# Plipbox.net
KiCad netlist of a schematic drawn in EAGLE
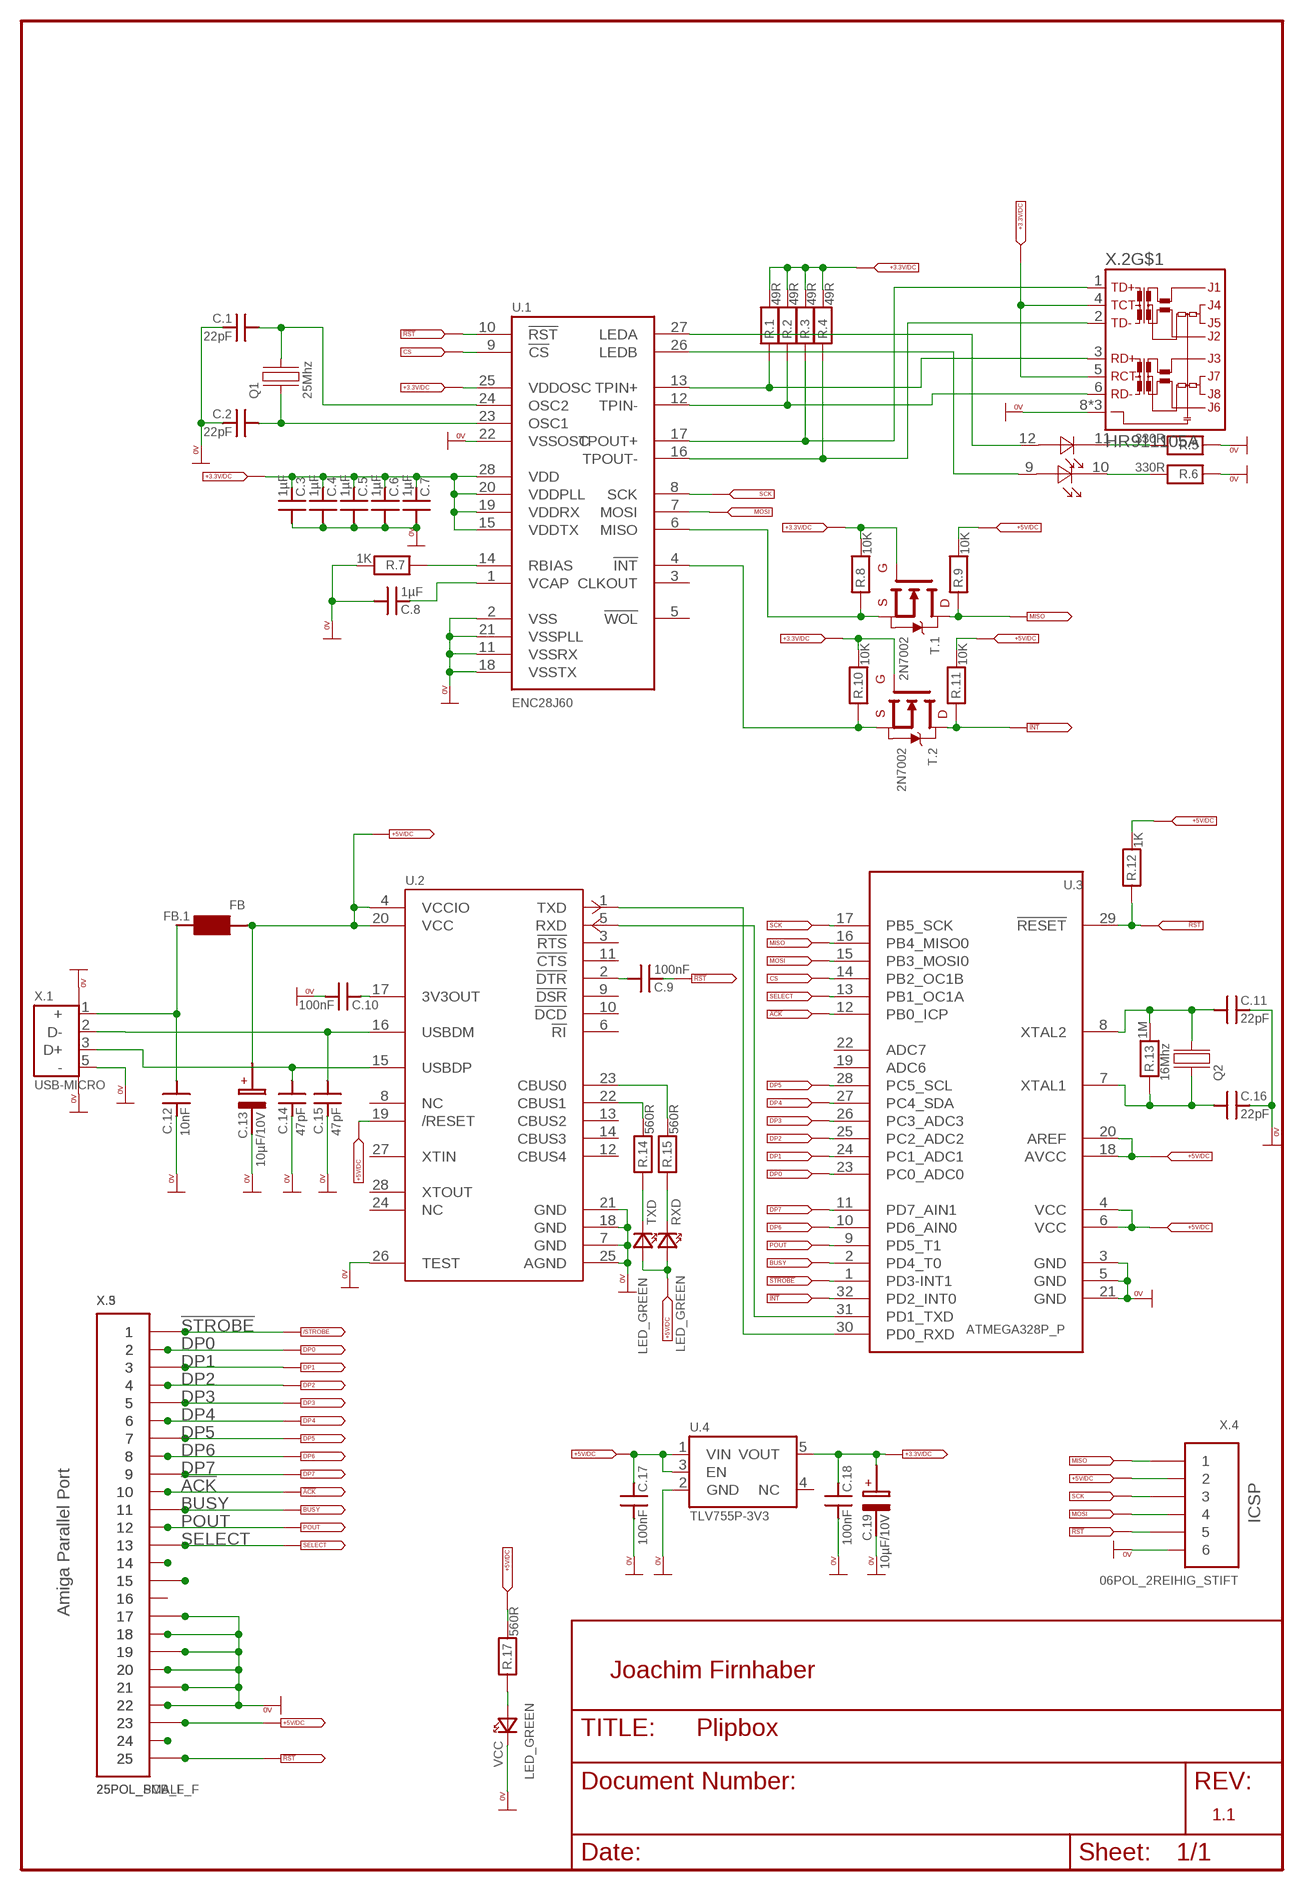
[diagram p0: schematic, sheet 1]

(export (version "E")
  (design (tool "Eeschema 10.0.6"))
  (components
    (comp (ref "C.1")
      (value "22pF")
      (footprint "eagle-import:0805")
      (libsource (lib "eagle-import") (part "CAPACITOR_SMD_0805"))
    )
    (comp (ref "C.2")
      (value "22pF")
      (footprint "eagle-import:0805")
      (libsource (lib "eagle-import") (part "CAPACITOR_SMD_0805"))
    )
    (comp (ref "C.3")
      (value "1µF")
      (footprint "eagle-import:0805")
      (libsource (lib "eagle-import") (part "CAPACITOR_SMD_0805"))
    )
    (comp (ref "C.4")
      (value "1µF")
      (footprint "eagle-import:0805")
      (libsource (lib "eagle-import") (part "CAPACITOR_SMD_0805"))
    )
    (comp (ref "C.5")
      (value "1µF")
      (footprint "eagle-import:0805")
      (libsource (lib "eagle-import") (part "CAPACITOR_SMD_0805"))
    )
    (comp (ref "C.6")
      (value "1µF")
      (footprint "eagle-import:0805")
      (libsource (lib "eagle-import") (part "CAPACITOR_SMD_0805"))
    )
    (comp (ref "C.7")
      (value "1µF")
      (footprint "eagle-import:0805")
      (libsource (lib "eagle-import") (part "CAPACITOR_SMD_0805"))
    )
    (comp (ref "C.8")
      (value "1µF")
      (footprint "eagle-import:0805")
      (libsource (lib "eagle-import") (part "CAPACITOR_SMD_0805"))
    )
    (comp (ref "C.9")
      (value "100nF")
      (footprint "eagle-import:0805")
      (libsource (lib "eagle-import") (part "CAPACITOR_SMD_0805"))
    )
    (comp (ref "C.10")
      (value "100nF")
      (footprint "eagle-import:0805")
      (libsource (lib "eagle-import") (part "CAPACITOR_SMD_0805"))
    )
    (comp (ref "C.11")
      (value "22pF")
      (footprint "eagle-import:0805")
      (libsource (lib "eagle-import") (part "CAPACITOR_SMD_0805"))
    )
    (comp (ref "C.12")
      (value "10nF")
      (footprint "eagle-import:0805")
      (libsource (lib "eagle-import") (part "CAPACITOR_SMD_0805"))
    )
    (comp (ref "C.13")
      (value "10µF/10V")
      (footprint "eagle-import:3216")
      (libsource (lib "eagle-import") (part "TANTAL_SMD_A(3216)"))
    )
    (comp (ref "C.14")
      (value "47pF")
      (footprint "eagle-import:0805")
      (libsource (lib "eagle-import") (part "CAPACITOR_SMD_0805"))
    )
    (comp (ref "C.15")
      (value "47pF")
      (footprint "eagle-import:0805")
      (libsource (lib "eagle-import") (part "CAPACITOR_SMD_0805"))
    )
    (comp (ref "C.16")
      (value "22pF")
      (footprint "eagle-import:0805")
      (libsource (lib "eagle-import") (part "CAPACITOR_SMD_0805"))
    )
    (comp (ref "C.17")
      (value "100nF")
      (footprint "eagle-import:0805")
      (libsource (lib "eagle-import") (part "CAPACITOR_SMD_0805"))
    )
    (comp (ref "C.18")
      (value "100nF")
      (footprint "eagle-import:0805")
      (libsource (lib "eagle-import") (part "CAPACITOR_SMD_0805"))
    )
    (comp (ref "C.19")
      (value "10µF/10V")
      (footprint "eagle-import:3216")
      (libsource (lib "eagle-import") (part "TANTAL_SMD_A(3216)"))
    )
    (comp (ref "FB.1")
      (value "FB")
      (footprint "eagle-import:0805")
      (libsource (lib "eagle-import") (part "FERRIT-BEAD"))
    )
    (comp (ref "Q1")
      (value "25Mhz")
      (footprint "eagle-import:3,4X2,7X0,75")
      (libsource (lib "eagle-import") (part "QUARZ_3,4X2,7"))
    )
    (comp (ref "Q2")
      (value "16Mhz")
      (footprint "eagle-import:3,4X2,7X0,75")
      (libsource (lib "eagle-import") (part "QUARZ_3,4X2,7"))
    )
    (comp (ref "R.1")
      (value "49R")
      (footprint "eagle-import:0805")
      (libsource (lib "eagle-import") (part "RESISTOR_SMD_0805"))
    )
    (comp (ref "R.2")
      (value "49R")
      (footprint "eagle-import:0805")
      (libsource (lib "eagle-import") (part "RESISTOR_SMD_0805"))
    )
    (comp (ref "R.3")
      (value "49R")
      (footprint "eagle-import:0805")
      (libsource (lib "eagle-import") (part "RESISTOR_SMD_0805"))
    )
    (comp (ref "R.4")
      (value "49R")
      (footprint "eagle-import:0805")
      (libsource (lib "eagle-import") (part "RESISTOR_SMD_0805"))
    )
    (comp (ref "R.5")
      (value "330R")
      (footprint "eagle-import:0805")
      (libsource (lib "eagle-import") (part "RESISTOR_SMD_0805"))
    )
    (comp (ref "R.6")
      (value "330R")
      (footprint "eagle-import:0805")
      (libsource (lib "eagle-import") (part "RESISTOR_SMD_0805"))
    )
    (comp (ref "R.7")
      (value "1K")
      (footprint "eagle-import:0805")
      (libsource (lib "eagle-import") (part "RESISTOR_SMD_0805"))
    )
    (comp (ref "R.8")
      (value "10K")
      (footprint "eagle-import:0805")
      (libsource (lib "eagle-import") (part "RESISTOR_SMD_0805"))
    )
    (comp (ref "R.9")
      (value "10K")
      (footprint "eagle-import:0805")
      (libsource (lib "eagle-import") (part "RESISTOR_SMD_0805"))
    )
    (comp (ref "R.10")
      (value "10K")
      (footprint "eagle-import:0805")
      (libsource (lib "eagle-import") (part "RESISTOR_SMD_0805"))
    )
    (comp (ref "R.11")
      (value "10K")
      (footprint "eagle-import:0805")
      (libsource (lib "eagle-import") (part "RESISTOR_SMD_0805"))
    )
    (comp (ref "R.12")
      (value "1K")
      (footprint "eagle-import:0805")
      (libsource (lib "eagle-import") (part "RESISTOR_SMD_0805"))
    )
    (comp (ref "R.13")
      (value "1M")
      (footprint "eagle-import:0805")
      (libsource (lib "eagle-import") (part "RESISTOR_SMD_0805"))
    )
    (comp (ref "R.14")
      (value "560R")
      (footprint "eagle-import:0805")
      (libsource (lib "eagle-import") (part "RESISTOR_SMD_0805"))
    )
    (comp (ref "R.15")
      (value "560R")
      (footprint "eagle-import:0805")
      (libsource (lib "eagle-import") (part "RESISTOR_SMD_0805"))
    )
    (comp (ref "R.17")
      (value "560R")
      (footprint "eagle-import:0805")
      (libsource (lib "eagle-import") (part "RESISTOR_SMD_0805"))
    )
    (comp (ref "RXD")
      (value "LED_GREEN")
      (footprint "eagle-import:0805")
      (libsource (lib "eagle-import") (part "LED_0805"))
    )
    (comp (ref "T.1")
      (value "2N7002")
      (footprint "eagle-import:SOT23")
      (libsource (lib "eagle-import") (part "2N7002_N"))
    )
    (comp (ref "T.2")
      (value "2N7002")
      (footprint "eagle-import:SOT23")
      (libsource (lib "eagle-import") (part "2N7002_N"))
    )
    (comp (ref "TXD")
      (value "LED_GREEN")
      (footprint "eagle-import:0805")
      (libsource (lib "eagle-import") (part "LED_0805"))
    )
    (comp (ref "U.1")
      (value "ENC28J60")
      (footprint "eagle-import:SSOP28")
      (libsource (lib "eagle-import") (part "EN28J60"))
    )
    (comp (ref "U.2")
      (value "FT232R_FT232RL")
      (footprint "eagle-import:SSOP28")
      (libsource (lib "eagle-import") (part "FT232R_FT232RL"))
    )
    (comp (ref "U.3")
      (value "ATMEGA328P_P")
      (footprint "eagle-import:LQFP32")
      (libsource (lib "eagle-import") (part "ATMEGA328P_P"))
    )
    (comp (ref "U.4")
      (value "TLV755P-3V3")
      (footprint "eagle-import:SOT23-5")
      (libsource (lib "eagle-import") (part "TLV755P"))
    )
    (comp (ref "VCC")
      (value "LED_GREEN")
      (footprint "eagle-import:0805")
      (libsource (lib "eagle-import") (part "LED_0805"))
    )
    (comp (ref "X.1")
      (value "USB-MICRO")
      (footprint "eagle-import:USB_MICRO")
      (libsource (lib "eagle-import") (part "USB-MICRO"))
    )
    (comp (ref "X.2")
      (value "HR911105A")
      (footprint "eagle-import:HR911105A")
      (libsource (lib "eagle-import") (part "HR911105A"))
    )
    (comp (ref "X.3")
      (value "25POL_PCB_F")
      (footprint "eagle-import:SUB-D_25F_L")
      (libsource (lib "eagle-import") (part "25POL_PCB_F"))
    )
    (comp (ref "X.4")
      (value "06POL_2REIHIG_STIFT")
      (footprint "eagle-import:STIFT_2_03")
      (libsource (lib "eagle-import") (part "06POL_2REIHIG_STIFT"))
    )
    (comp (ref "X.5")
      (value "25POL_SMALL_F")
      (footprint "eagle-import:SUB-D_25F_ONLY")
      (libsource (lib "eagle-import") (part "25POL_SMALL_F"))
    )
  )
  (nets
    (net (code "1") (name "!ACK") (class "Default")
      (node (ref "U.3") (pin "12") (pinfunction "PB0_ICP_12") (pintype "bidirectional"))
      (node (ref "X.3") (pin "10") (pinfunction "10_10") (pintype "passive"))
      (node (ref "X.5") (pin "10") (pinfunction "10_10") (pintype "passive"))
    )
    (net (code "2") (name "!INT") (class "Default")
      (node (ref "R.11") (pin "1") (pinfunction "1_1") (pintype "passive"))
      (node (ref "T.2") (pin "3") (pinfunction "DRAIN_3") (pintype "passive"))
      (node (ref "U.3") (pin "32") (pinfunction "PD2_INT0_32") (pintype "bidirectional"))
    )
    (net (code "3") (name "!RST") (class "Default")
      (node (ref "C.9") (pin "2") (pinfunction "2_2") (pintype "passive"))
      (node (ref "R.12") (pin "1") (pinfunction "1_1") (pintype "passive"))
      (node (ref "U.1") (pin "10") (pinfunction "~{RST}_10") (pintype "bidirectional"))
      (node (ref "U.3") (pin "29") (pinfunction "~{RESET}_29") (pintype "bidirectional"))
      (node (ref "X.3") (pin "25") (pinfunction "25_25") (pintype "passive"))
      (node (ref "X.4") (pin "5") (pinfunction "5_5") (pintype "passive"))
      (node (ref "X.5") (pin "25") (pinfunction "25_25") (pintype "passive"))
    )
    (net (code "4") (name "!STROBE") (class "Default")
      (node (ref "U.3") (pin "1") (pinfunction "PD3-INT1_1") (pintype "bidirectional"))
      (node (ref "X.3") (pin "1") (pinfunction "1_1") (pintype "passive"))
      (node (ref "X.5") (pin "1") (pinfunction "1_1") (pintype "passive"))
    )
    (net (code "5") (name "+3.3V-IN") (class "Default")
      (node (ref "C.18") (pin "2") (pinfunction "2_2") (pintype "passive"))
      (node (ref "C.19") (pin "+") (pinfunction "+_+") (pintype "passive"))
      (node (ref "C.3") (pin "2") (pinfunction "2_2") (pintype "passive"))
      (node (ref "C.4") (pin "2") (pinfunction "2_2") (pintype "passive"))
      (node (ref "C.5") (pin "2") (pinfunction "2_2") (pintype "passive"))
      (node (ref "C.6") (pin "2") (pinfunction "2_2") (pintype "passive"))
      (node (ref "C.7") (pin "2") (pinfunction "2_2") (pintype "passive"))
      (node (ref "R.1") (pin "2") (pinfunction "2_2") (pintype "passive"))
      (node (ref "R.10") (pin "2") (pinfunction "2_2") (pintype "passive"))
      (node (ref "R.2") (pin "2") (pinfunction "2_2") (pintype "passive"))
      (node (ref "R.3") (pin "2") (pinfunction "2_2") (pintype "passive"))
      (node (ref "R.4") (pin "2") (pinfunction "2_2") (pintype "passive"))
      (node (ref "R.8") (pin "2") (pinfunction "2_2") (pintype "passive"))
      (node (ref "T.1") (pin "1") (pinfunction "GATE_1") (pintype "passive"))
      (node (ref "T.2") (pin "1") (pinfunction "GATE_1") (pintype "passive"))
      (node (ref "U.1") (pin "15") (pinfunction "VDDTX_15") (pintype "bidirectional"))
      (node (ref "U.1") (pin "19") (pinfunction "VDDRX_19") (pintype "bidirectional"))
      (node (ref "U.1") (pin "20") (pinfunction "VDDPLL_20") (pintype "bidirectional"))
      (node (ref "U.1") (pin "25") (pinfunction "VDDOSC_25") (pintype "bidirectional"))
      (node (ref "U.1") (pin "28") (pinfunction "VDD_28") (pintype "bidirectional"))
      (node (ref "U.4") (pin "5") (pinfunction "VOUT_5") (pintype "bidirectional"))
      (node (ref "X.2") (pin "4") (pinfunction "TCT-_4") (pintype "passive"))
      (node (ref "X.2") (pin "5") (pinfunction "RCT-_5") (pintype "passive"))
    )
    (net (code "6") (name "+5V-IN") (class "Default")
      (node (ref "C.13") (pin "+") (pinfunction "+_+") (pintype "passive"))
      (node (ref "C.17") (pin "2") (pinfunction "2_2") (pintype "passive"))
      (node (ref "FB.1") (pin "1") (pinfunction "1_1") (pintype "passive"))
      (node (ref "R.11") (pin "2") (pinfunction "2_2") (pintype "passive"))
      (node (ref "R.12") (pin "2") (pinfunction "2_2") (pintype "passive"))
      (node (ref "R.17") (pin "2") (pinfunction "2_2") (pintype "passive"))
      (node (ref "R.9") (pin "2") (pinfunction "2_2") (pintype "passive"))
      (node (ref "RXD") (pin "A") (pinfunction "ANODE_A") (pintype "passive"))
      (node (ref "TXD") (pin "A") (pinfunction "ANODE_A") (pintype "passive"))
      (node (ref "U.2") (pin "19") (pinfunction "/RESET_19") (pintype "bidirectional"))
      (node (ref "U.2") (pin "20") (pinfunction "VCC_20") (pintype "bidirectional"))
      (node (ref "U.2") (pin "4") (pinfunction "VCCIO_4") (pintype "bidirectional"))
      (node (ref "U.3") (pin "18") (pinfunction "AVCC_18") (pintype "bidirectional"))
      (node (ref "U.3") (pin "20") (pinfunction "AREF_20") (pintype "bidirectional"))
      (node (ref "U.3") (pin "4") (pinfunction "VCC_4") (pintype "bidirectional"))
      (node (ref "U.3") (pin "6") (pinfunction "VCC_6") (pintype "bidirectional"))
      (node (ref "U.4") (pin "1") (pinfunction "VIN_1") (pintype "bidirectional"))
      (node (ref "U.4") (pin "3") (pinfunction "EN_3") (pintype "bidirectional"))
      (node (ref "X.3") (pin "23") (pinfunction "23_23") (pintype "passive"))
      (node (ref "X.4") (pin "2") (pinfunction "2_2") (pintype "passive"))
      (node (ref "X.5") (pin "23") (pinfunction "23_23") (pintype "passive"))
    )
    (net (code "7") (name "0V") (class "Default")
      (node (ref "C.1") (pin "2") (pinfunction "2_2") (pintype "passive"))
      (node (ref "C.10") (pin "1") (pinfunction "1_1") (pintype "passive"))
      (node (ref "C.11") (pin "2") (pinfunction "2_2") (pintype "passive"))
      (node (ref "C.12") (pin "2") (pinfunction "2_2") (pintype "passive"))
      (node (ref "C.13") (pin "-") (pinfunction "-_-") (pintype "passive"))
      (node (ref "C.14") (pin "2") (pinfunction "2_2") (pintype "passive"))
      (node (ref "C.15") (pin "2") (pinfunction "2_2") (pintype "passive"))
      (node (ref "C.16") (pin "2") (pinfunction "2_2") (pintype "passive"))
      (node (ref "C.17") (pin "1") (pinfunction "1_1") (pintype "passive"))
      (node (ref "C.18") (pin "1") (pinfunction "1_1") (pintype "passive"))
      (node (ref "C.19") (pin "-") (pinfunction "-_-") (pintype "passive"))
      (node (ref "C.2") (pin "2") (pinfunction "2_2") (pintype "passive"))
      (node (ref "C.3") (pin "1") (pinfunction "1_1") (pintype "passive"))
      (node (ref "C.4") (pin "1") (pinfunction "1_1") (pintype "passive"))
      (node (ref "C.5") (pin "1") (pinfunction "1_1") (pintype "passive"))
      (node (ref "C.6") (pin "1") (pinfunction "1_1") (pintype "passive"))
      (node (ref "C.7") (pin "1") (pinfunction "1_1") (pintype "passive"))
      (node (ref "C.8") (pin "1") (pinfunction "1_1") (pintype "passive"))
      (node (ref "R.5") (pin "1") (pinfunction "1_1") (pintype "passive"))
      (node (ref "R.6") (pin "1") (pinfunction "1_1") (pintype "passive"))
      (node (ref "R.7") (pin "2") (pinfunction "2_2") (pintype "passive"))
      (node (ref "U.1") (pin "11") (pinfunction "VSSRX_11") (pintype "bidirectional"))
      (node (ref "U.1") (pin "18") (pinfunction "VSSTX_18") (pintype "bidirectional"))
      (node (ref "U.1") (pin "2") (pinfunction "VSS_2") (pintype "bidirectional"))
      (node (ref "U.1") (pin "21") (pinfunction "VSSPLL_21") (pintype "bidirectional"))
      (node (ref "U.1") (pin "22") (pinfunction "VSSOSC_22") (pintype "bidirectional"))
      (node (ref "U.2") (pin "18") (pinfunction "GND_18") (pintype "bidirectional"))
      (node (ref "U.2") (pin "21") (pinfunction "GND_21") (pintype "bidirectional"))
      (node (ref "U.2") (pin "25") (pinfunction "AGND_25") (pintype "bidirectional"))
      (node (ref "U.2") (pin "26") (pinfunction "TEST_26") (pintype "bidirectional"))
      (node (ref "U.2") (pin "7") (pinfunction "GND_7") (pintype "bidirectional"))
      (node (ref "U.3") (pin "21") (pinfunction "GND_21") (pintype "bidirectional"))
      (node (ref "U.3") (pin "3") (pinfunction "GND_3") (pintype "bidirectional"))
      (node (ref "U.3") (pin "5") (pinfunction "GND_5") (pintype "bidirectional"))
      (node (ref "U.4") (pin "2") (pinfunction "GND_2") (pintype "bidirectional"))
      (node (ref "VCC") (pin "K") (pinfunction "KATHODE_K") (pintype "passive"))
      (node (ref "X.1") (pin "5") (pinfunction "-_5") (pintype "bidirectional"))
      (node (ref "X.1") (pin "6") (pinfunction "GND_6") (pintype "bidirectional"))
      (node (ref "X.1") (pin "7") (pinfunction "GND_7") (pintype "bidirectional"))
      (node (ref "X.2") (pin "8") (pinfunction "GND_8") (pintype "passive"))
      (node (ref "X.2") (pin "Z1") (pinfunction "GND_Z1") (pintype "passive"))
      (node (ref "X.2") (pin "Z2") (pinfunction "GND_Z2") (pintype "passive"))
      (node (ref "X.3") (pin "17") (pinfunction "17_17") (pintype "passive"))
      (node (ref "X.3") (pin "18") (pinfunction "18_18") (pintype "passive"))
      (node (ref "X.3") (pin "19") (pinfunction "19_19") (pintype "passive"))
      (node (ref "X.3") (pin "20") (pinfunction "20_20") (pintype "passive"))
      (node (ref "X.3") (pin "21") (pinfunction "21_21") (pintype "passive"))
      (node (ref "X.3") (pin "22") (pinfunction "22_22") (pintype "passive"))
      (node (ref "X.4") (pin "6") (pinfunction "6_6") (pintype "passive"))
      (node (ref "X.5") (pin "17") (pinfunction "17_17") (pintype "passive"))
      (node (ref "X.5") (pin "18") (pinfunction "18_18") (pintype "passive"))
      (node (ref "X.5") (pin "19") (pinfunction "19_19") (pintype "passive"))
      (node (ref "X.5") (pin "20") (pinfunction "20_20") (pintype "passive"))
      (node (ref "X.5") (pin "21") (pinfunction "21_21") (pintype "passive"))
      (node (ref "X.5") (pin "22") (pinfunction "22_22") (pintype "passive"))
    )
    (net (code "8") (name "BUSY") (class "Default")
      (node (ref "U.3") (pin "2") (pinfunction "PD4_T0_2") (pintype "bidirectional"))
      (node (ref "X.3") (pin "11") (pinfunction "11_11") (pintype "passive"))
      (node (ref "X.5") (pin "11") (pinfunction "11_11") (pintype "passive"))
    )
    (net (code "9") (name "CS") (class "Default")
      (node (ref "U.1") (pin "9") (pinfunction "~{CS}_9") (pintype "bidirectional"))
      (node (ref "U.3") (pin "14") (pinfunction "PB2_OC1B_14") (pintype "bidirectional"))
    )
    (net (code "10") (name "DP0") (class "Default")
      (node (ref "U.3") (pin "23") (pinfunction "PC0_ADC0_23") (pintype "bidirectional"))
      (node (ref "X.3") (pin "2") (pinfunction "2_2") (pintype "passive"))
      (node (ref "X.5") (pin "2") (pinfunction "2_2") (pintype "passive"))
    )
    (net (code "11") (name "DP1") (class "Default")
      (node (ref "U.3") (pin "24") (pinfunction "PC1_ADC1_24") (pintype "bidirectional"))
      (node (ref "X.3") (pin "3") (pinfunction "3_3") (pintype "passive"))
      (node (ref "X.5") (pin "3") (pinfunction "3_3") (pintype "passive"))
    )
    (net (code "12") (name "DP2") (class "Default")
      (node (ref "U.3") (pin "25") (pinfunction "PC2_ADC2_25") (pintype "bidirectional"))
      (node (ref "X.3") (pin "4") (pinfunction "4_4") (pintype "passive"))
      (node (ref "X.5") (pin "4") (pinfunction "4_4") (pintype "passive"))
    )
    (net (code "13") (name "DP3") (class "Default")
      (node (ref "U.3") (pin "26") (pinfunction "PC3_ADC3_26") (pintype "bidirectional"))
      (node (ref "X.3") (pin "5") (pinfunction "5_5") (pintype "passive"))
      (node (ref "X.5") (pin "5") (pinfunction "5_5") (pintype "passive"))
    )
    (net (code "14") (name "DP4") (class "Default")
      (node (ref "U.3") (pin "27") (pinfunction "PC4_SDA_27") (pintype "bidirectional"))
      (node (ref "X.3") (pin "6") (pinfunction "6_6") (pintype "passive"))
      (node (ref "X.5") (pin "6") (pinfunction "6_6") (pintype "passive"))
    )
    (net (code "15") (name "DP5") (class "Default")
      (node (ref "U.3") (pin "28") (pinfunction "PC5_SCL_28") (pintype "bidirectional"))
      (node (ref "X.3") (pin "7") (pinfunction "7_7") (pintype "passive"))
      (node (ref "X.5") (pin "7") (pinfunction "7_7") (pintype "passive"))
    )
    (net (code "16") (name "DP6") (class "Default")
      (node (ref "U.3") (pin "10") (pinfunction "PD6_AIN0_10") (pintype "bidirectional"))
      (node (ref "X.3") (pin "8") (pinfunction "8_8") (pintype "passive"))
      (node (ref "X.5") (pin "8") (pinfunction "8_8") (pintype "passive"))
    )
    (net (code "17") (name "DP7") (class "Default")
      (node (ref "U.3") (pin "11") (pinfunction "PD7_AIN1_11") (pintype "bidirectional"))
      (node (ref "X.3") (pin "9") (pinfunction "9_9") (pintype "passive"))
      (node (ref "X.5") (pin "9") (pinfunction "9_9") (pintype "passive"))
    )
    (net (code "18") (name "MISO") (class "Default")
      (node (ref "R.9") (pin "1") (pinfunction "1_1") (pintype "passive"))
      (node (ref "T.1") (pin "3") (pinfunction "DRAIN_3") (pintype "passive"))
      (node (ref "U.3") (pin "16") (pinfunction "PB4_MISO0_16") (pintype "bidirectional"))
      (node (ref "X.4") (pin "1") (pinfunction "1_1") (pintype "passive"))
    )
    (net (code "19") (name "MOSI") (class "Default")
      (node (ref "U.1") (pin "7") (pinfunction "MOSI_7") (pintype "bidirectional"))
      (node (ref "U.3") (pin "15") (pinfunction "PB3_MOSI0_15") (pintype "bidirectional"))
      (node (ref "X.4") (pin "4") (pinfunction "4_4") (pintype "passive"))
    )
    (net (code "20") (name "Net-(Q1-XTAL1)") (class "Default")
      (node (ref "C.2") (pin "1") (pinfunction "1_1") (pintype "passive"))
      (node (ref "Q1") (pin "2") (pinfunction "XTAL1_2") (pintype "bidirectional"))
      (node (ref "U.1") (pin "23") (pinfunction "OSC1_23") (pintype "bidirectional"))
    )
    (net (code "21") (name "Net-(Q1-XTAL2)") (class "Default")
      (node (ref "C.1") (pin "1") (pinfunction "1_1") (pintype "passive"))
      (node (ref "Q1") (pin "4") (pinfunction "XTAL2_4") (pintype "bidirectional"))
      (node (ref "U.1") (pin "24") (pinfunction "OSC2_24") (pintype "bidirectional"))
    )
    (net (code "22") (name "Net-(Q2-XTAL1)") (class "Default")
      (node (ref "C.16") (pin "1") (pinfunction "1_1") (pintype "passive"))
      (node (ref "Q2") (pin "2") (pinfunction "XTAL1_2") (pintype "bidirectional"))
      (node (ref "R.13") (pin "1") (pinfunction "1_1") (pintype "passive"))
      (node (ref "U.3") (pin "7") (pinfunction "XTAL1_7") (pintype "bidirectional"))
    )
    (net (code "23") (name "Net-(Q2-XTAL2)") (class "Default")
      (node (ref "C.11") (pin "1") (pinfunction "1_1") (pintype "passive"))
      (node (ref "Q2") (pin "4") (pinfunction "XTAL2_4") (pintype "bidirectional"))
      (node (ref "R.13") (pin "2") (pinfunction "2_2") (pintype "passive"))
      (node (ref "U.3") (pin "8") (pinfunction "XTAL2_8") (pintype "bidirectional"))
    )
    (net (code "24") (name "Net-(RXD-KATHODE)") (class "Default")
      (node (ref "R.15") (pin "1") (pinfunction "1_1") (pintype "passive"))
      (node (ref "RXD") (pin "K") (pinfunction "KATHODE_K") (pintype "passive"))
    )
    (net (code "25") (name "Net-(T.1-SOURCE)") (class "Default")
      (node (ref "R.8") (pin "1") (pinfunction "1_1") (pintype "passive"))
      (node (ref "T.1") (pin "2") (pinfunction "SOURCE_2") (pintype "passive"))
      (node (ref "U.1") (pin "6") (pinfunction "MISO_6") (pintype "bidirectional"))
    )
    (net (code "26") (name "Net-(T.2-SOURCE)") (class "Default")
      (node (ref "R.10") (pin "1") (pinfunction "1_1") (pintype "passive"))
      (node (ref "T.2") (pin "2") (pinfunction "SOURCE_2") (pintype "passive"))
      (node (ref "U.1") (pin "4") (pinfunction "~{INT}_4") (pintype "bidirectional"))
    )
    (net (code "27") (name "Net-(TXD-KATHODE)") (class "Default")
      (node (ref "R.14") (pin "1") (pinfunction "1_1") (pintype "passive"))
      (node (ref "TXD") (pin "K") (pinfunction "KATHODE_K") (pintype "passive"))
    )
    (net (code "28") (name "Net-(U.1-LEDA)") (class "Default")
      (node (ref "U.1") (pin "27") (pinfunction "LEDA_27") (pintype "bidirectional"))
      (node (ref "X.2") (pin "12") (pinfunction "A_12") (pintype "bidirectional"))
    )
    (net (code "29") (name "Net-(U.1-LEDB)") (class "Default")
      (node (ref "U.1") (pin "26") (pinfunction "LEDB_26") (pintype "bidirectional"))
      (node (ref "X.2") (pin "9") (pinfunction "A_9") (pintype "bidirectional"))
    )
    (net (code "30") (name "Net-(U.1-RBIAS)") (class "Default")
      (node (ref "R.7") (pin "1") (pinfunction "1_1") (pintype "passive"))
      (node (ref "U.1") (pin "14") (pinfunction "RBIAS_14") (pintype "bidirectional"))
    )
    (net (code "31") (name "Net-(U.1-TPIN+)") (class "Default")
      (node (ref "R.1") (pin "1") (pinfunction "1_1") (pintype "passive"))
      (node (ref "U.1") (pin "13") (pinfunction "TPIN+_13") (pintype "bidirectional"))
      (node (ref "X.2") (pin "3") (pinfunction "RD+_3") (pintype "passive"))
    )
    (net (code "32") (name "Net-(U.1-TPIN-)") (class "Default")
      (node (ref "R.2") (pin "1") (pinfunction "1_1") (pintype "passive"))
      (node (ref "U.1") (pin "12") (pinfunction "TPIN-_12") (pintype "bidirectional"))
      (node (ref "X.2") (pin "6") (pinfunction "RD-_6") (pintype "passive"))
    )
    (net (code "33") (name "Net-(U.1-TPOUT+)") (class "Default")
      (node (ref "R.3") (pin "1") (pinfunction "1_1") (pintype "passive"))
      (node (ref "U.1") (pin "17") (pinfunction "TPOUT+_17") (pintype "bidirectional"))
      (node (ref "X.2") (pin "1") (pinfunction "TD+_1") (pintype "passive"))
    )
    (net (code "34") (name "Net-(U.1-TPOUT-)") (class "Default")
      (node (ref "R.4") (pin "1") (pinfunction "1_1") (pintype "passive"))
      (node (ref "U.1") (pin "16") (pinfunction "TPOUT-_16") (pintype "bidirectional"))
      (node (ref "X.2") (pin "2") (pinfunction "TD-_2") (pintype "passive"))
    )
    (net (code "35") (name "Net-(U.1-VCAP)") (class "Default")
      (node (ref "C.8") (pin "2") (pinfunction "2_2") (pintype "passive"))
      (node (ref "U.1") (pin "1") (pinfunction "VCAP_1") (pintype "bidirectional"))
    )
    (net (code "36") (name "Net-(U.2-3V3OUT)") (class "Default")
      (node (ref "C.10") (pin "2") (pinfunction "2_2") (pintype "passive"))
      (node (ref "U.2") (pin "17") (pinfunction "3V3OUT_17") (pintype "bidirectional"))
    )
    (net (code "37") (name "Net-(U.2-CBUS0)") (class "Default")
      (node (ref "R.15") (pin "2") (pinfunction "2_2") (pintype "passive"))
      (node (ref "U.2") (pin "23") (pinfunction "CBUS0_23") (pintype "bidirectional"))
    )
    (net (code "38") (name "Net-(U.2-CBUS1)") (class "Default")
      (node (ref "R.14") (pin "2") (pinfunction "2_2") (pintype "passive"))
      (node (ref "U.2") (pin "22") (pinfunction "CBUS1_22") (pintype "bidirectional"))
    )
    (net (code "39") (name "Net-(U.2-RXD)") (class "Default")
      (node (ref "U.2") (pin "5") (pinfunction "RXD_5") (pintype "bidirectional"))
      (node (ref "U.3") (pin "31") (pinfunction "PD1_TXD_31") (pintype "bidirectional"))
    )
    (net (code "40") (name "Net-(U.2-TXD)") (class "Default")
      (node (ref "U.2") (pin "1") (pinfunction "TXD_1") (pintype "bidirectional"))
      (node (ref "U.3") (pin "30") (pinfunction "PD0_RXD_30") (pintype "bidirectional"))
    )
    (net (code "41") (name "Net-(U.2-USBDM)") (class "Default")
      (node (ref "C.15") (pin "1") (pinfunction "1_1") (pintype "passive"))
      (node (ref "U.2") (pin "16") (pinfunction "USBDM_16") (pintype "bidirectional"))
      (node (ref "X.1") (pin "2") (pinfunction "D-_2") (pintype "bidirectional"))
    )
    (net (code "42") (name "Net-(U.2-USBDP)") (class "Default")
      (node (ref "C.14") (pin "1") (pinfunction "1_1") (pintype "passive"))
      (node (ref "U.2") (pin "15") (pinfunction "USBDP_15") (pintype "bidirectional"))
      (node (ref "X.1") (pin "3") (pinfunction "D+_3") (pintype "bidirectional"))
    )
    (net (code "43") (name "Net-(U.2-~{DTR})") (class "Default")
      (node (ref "C.9") (pin "1") (pinfunction "1_1") (pintype "passive"))
      (node (ref "U.2") (pin "2") (pinfunction "~{DTR}_2") (pintype "bidirectional"))
    )
    (net (code "44") (name "Net-(VCC-ANODE)") (class "Default")
      (node (ref "R.17") (pin "1") (pinfunction "1_1") (pintype "passive"))
      (node (ref "VCC") (pin "A") (pinfunction "ANODE_A") (pintype "passive"))
    )
    (net (code "45") (name "Net-(X.1-+)") (class "Default")
      (node (ref "C.12") (pin "1") (pinfunction "1_1") (pintype "passive"))
      (node (ref "FB.1") (pin "2") (pinfunction "2_2") (pintype "passive"))
      (node (ref "X.1") (pin "1") (pinfunction "+_1") (pintype "bidirectional"))
    )
    (net (code "46") (name "Net-(X.2B-K)") (class "Default")
      (node (ref "R.5") (pin "2") (pinfunction "2_2") (pintype "passive"))
      (node (ref "X.2") (pin "11") (pinfunction "K_11") (pintype "bidirectional"))
    )
    (net (code "47") (name "Net-(X.2C-K)") (class "Default")
      (node (ref "R.6") (pin "2") (pinfunction "2_2") (pintype "passive"))
      (node (ref "X.2") (pin "10") (pinfunction "K_10") (pintype "bidirectional"))
    )
    (net (code "48") (name "Net-(X.3-Pad14)") (class "Default")
      (node (ref "X.3") (pin "14") (pinfunction "14_14") (pintype "passive"))
      (node (ref "X.5") (pin "14") (pinfunction "14_14") (pintype "passive"))
    )
    (net (code "49") (name "Net-(X.3-Pad15)") (class "Default")
      (node (ref "X.3") (pin "15") (pinfunction "15_15") (pintype "passive"))
      (node (ref "X.5") (pin "15") (pinfunction "15_15") (pintype "passive"))
    )
    (net (code "50") (name "Net-(X.3-Pad16)") (class "Default")
      (node (ref "X.3") (pin "16") (pinfunction "16_16") (pintype "passive"))
      (node (ref "X.5") (pin "16") (pinfunction "16_16") (pintype "passive"))
    )
    (net (code "51") (name "Net-(X.3-Pad24)") (class "Default")
      (node (ref "X.3") (pin "24") (pinfunction "24_24") (pintype "passive"))
      (node (ref "X.5") (pin "24") (pinfunction "24_24") (pintype "passive"))
    )
    (net (code "52") (name "POUT") (class "Default")
      (node (ref "U.3") (pin "9") (pinfunction "PD5_T1_9") (pintype "bidirectional"))
      (node (ref "X.3") (pin "12") (pinfunction "12_12") (pintype "passive"))
      (node (ref "X.5") (pin "12") (pinfunction "12_12") (pintype "passive"))
    )
    (net (code "53") (name "SCK") (class "Default")
      (node (ref "U.1") (pin "8") (pinfunction "SCK_8") (pintype "bidirectional"))
      (node (ref "U.3") (pin "17") (pinfunction "PB5_SCK_17") (pintype "bidirectional"))
      (node (ref "X.4") (pin "3") (pinfunction "3_3") (pintype "passive"))
    )
    (net (code "54") (name "SELECT") (class "Default")
      (node (ref "U.3") (pin "13") (pinfunction "PB1_OC1A_13") (pintype "bidirectional"))
      (node (ref "X.3") (pin "13") (pinfunction "13_13") (pintype "passive"))
      (node (ref "X.5") (pin "13") (pinfunction "13_13") (pintype "passive"))
    )
    (net (code "55") (name "unconnected-(U.1-CLKOUT-Pad3)") (class "Default")
      (node (ref "U.1") (pin "3") (pinfunction "CLKOUT_3") (pintype "bidirectional"))
    )
    (net (code "56") (name "unconnected-(U.1-~{WOL}-Pad5)") (class "Default")
      (node (ref "U.1") (pin "5") (pinfunction "~{WOL}_5") (pintype "bidirectional"))
    )
    (net (code "57") (name "unconnected-(U.2-CBUS2-Pad13)") (class "Default")
      (node (ref "U.2") (pin "13") (pinfunction "CBUS2_13") (pintype "bidirectional"))
    )
    (net (code "58") (name "unconnected-(U.2-CBUS3-Pad14)") (class "Default")
      (node (ref "U.2") (pin "14") (pinfunction "CBUS3_14") (pintype "bidirectional"))
    )
    (net (code "59") (name "unconnected-(U.2-CBUS4-Pad12)") (class "Default")
      (node (ref "U.2") (pin "12") (pinfunction "CBUS4_12") (pintype "bidirectional"))
    )
    (net (code "60") (name "unconnected-(U.2-NC-Pad8)") (class "Default")
      (node (ref "U.2") (pin "8") (pinfunction "NC_8") (pintype "bidirectional"))
    )
    (net (code "61") (name "unconnected-(U.2-NC-Pad24)") (class "Default")
      (node (ref "U.2") (pin "24") (pinfunction "NC_24") (pintype "bidirectional"))
    )
    (net (code "62") (name "unconnected-(U.2-XTIN-Pad27)") (class "Default")
      (node (ref "U.2") (pin "27") (pinfunction "XTIN_27") (pintype "bidirectional"))
    )
    (net (code "63") (name "unconnected-(U.2-XTOUT-Pad28)") (class "Default")
      (node (ref "U.2") (pin "28") (pinfunction "XTOUT_28") (pintype "bidirectional"))
    )
    (net (code "64") (name "unconnected-(U.2-~{CTS}-Pad11)") (class "Default")
      (node (ref "U.2") (pin "11") (pinfunction "~{CTS}_11") (pintype "bidirectional"))
    )
    (net (code "65") (name "unconnected-(U.2-~{DCD}-Pad10)") (class "Default")
      (node (ref "U.2") (pin "10") (pinfunction "~{DCD}_10") (pintype "bidirectional"))
    )
    (net (code "66") (name "unconnected-(U.2-~{DSR}-Pad9)") (class "Default")
      (node (ref "U.2") (pin "9") (pinfunction "~{DSR}_9") (pintype "bidirectional"))
    )
    (net (code "67") (name "unconnected-(U.2-~{RI}-Pad6)") (class "Default")
      (node (ref "U.2") (pin "6") (pinfunction "~{RI}_6") (pintype "bidirectional"))
    )
    (net (code "68") (name "unconnected-(U.2-~{RTS}-Pad3)") (class "Default")
      (node (ref "U.2") (pin "3") (pinfunction "~{RTS}_3") (pintype "bidirectional"))
    )
    (net (code "69") (name "unconnected-(U.3-ADC6-Pad19)") (class "Default")
      (node (ref "U.3") (pin "19") (pinfunction "ADC6_19") (pintype "bidirectional"))
    )
    (net (code "70") (name "unconnected-(U.3-ADC7-Pad22)") (class "Default")
      (node (ref "U.3") (pin "22") (pinfunction "ADC7_22") (pintype "bidirectional"))
    )
    (net (code "71") (name "unconnected-(U.4-NC-Pad4)") (class "Default")
      (node (ref "U.4") (pin "4") (pinfunction "NC_4") (pintype "bidirectional"))
    )
  )
)
